# schematic_design.net
KiCad netlist of a schematic drawn in EasyEDA
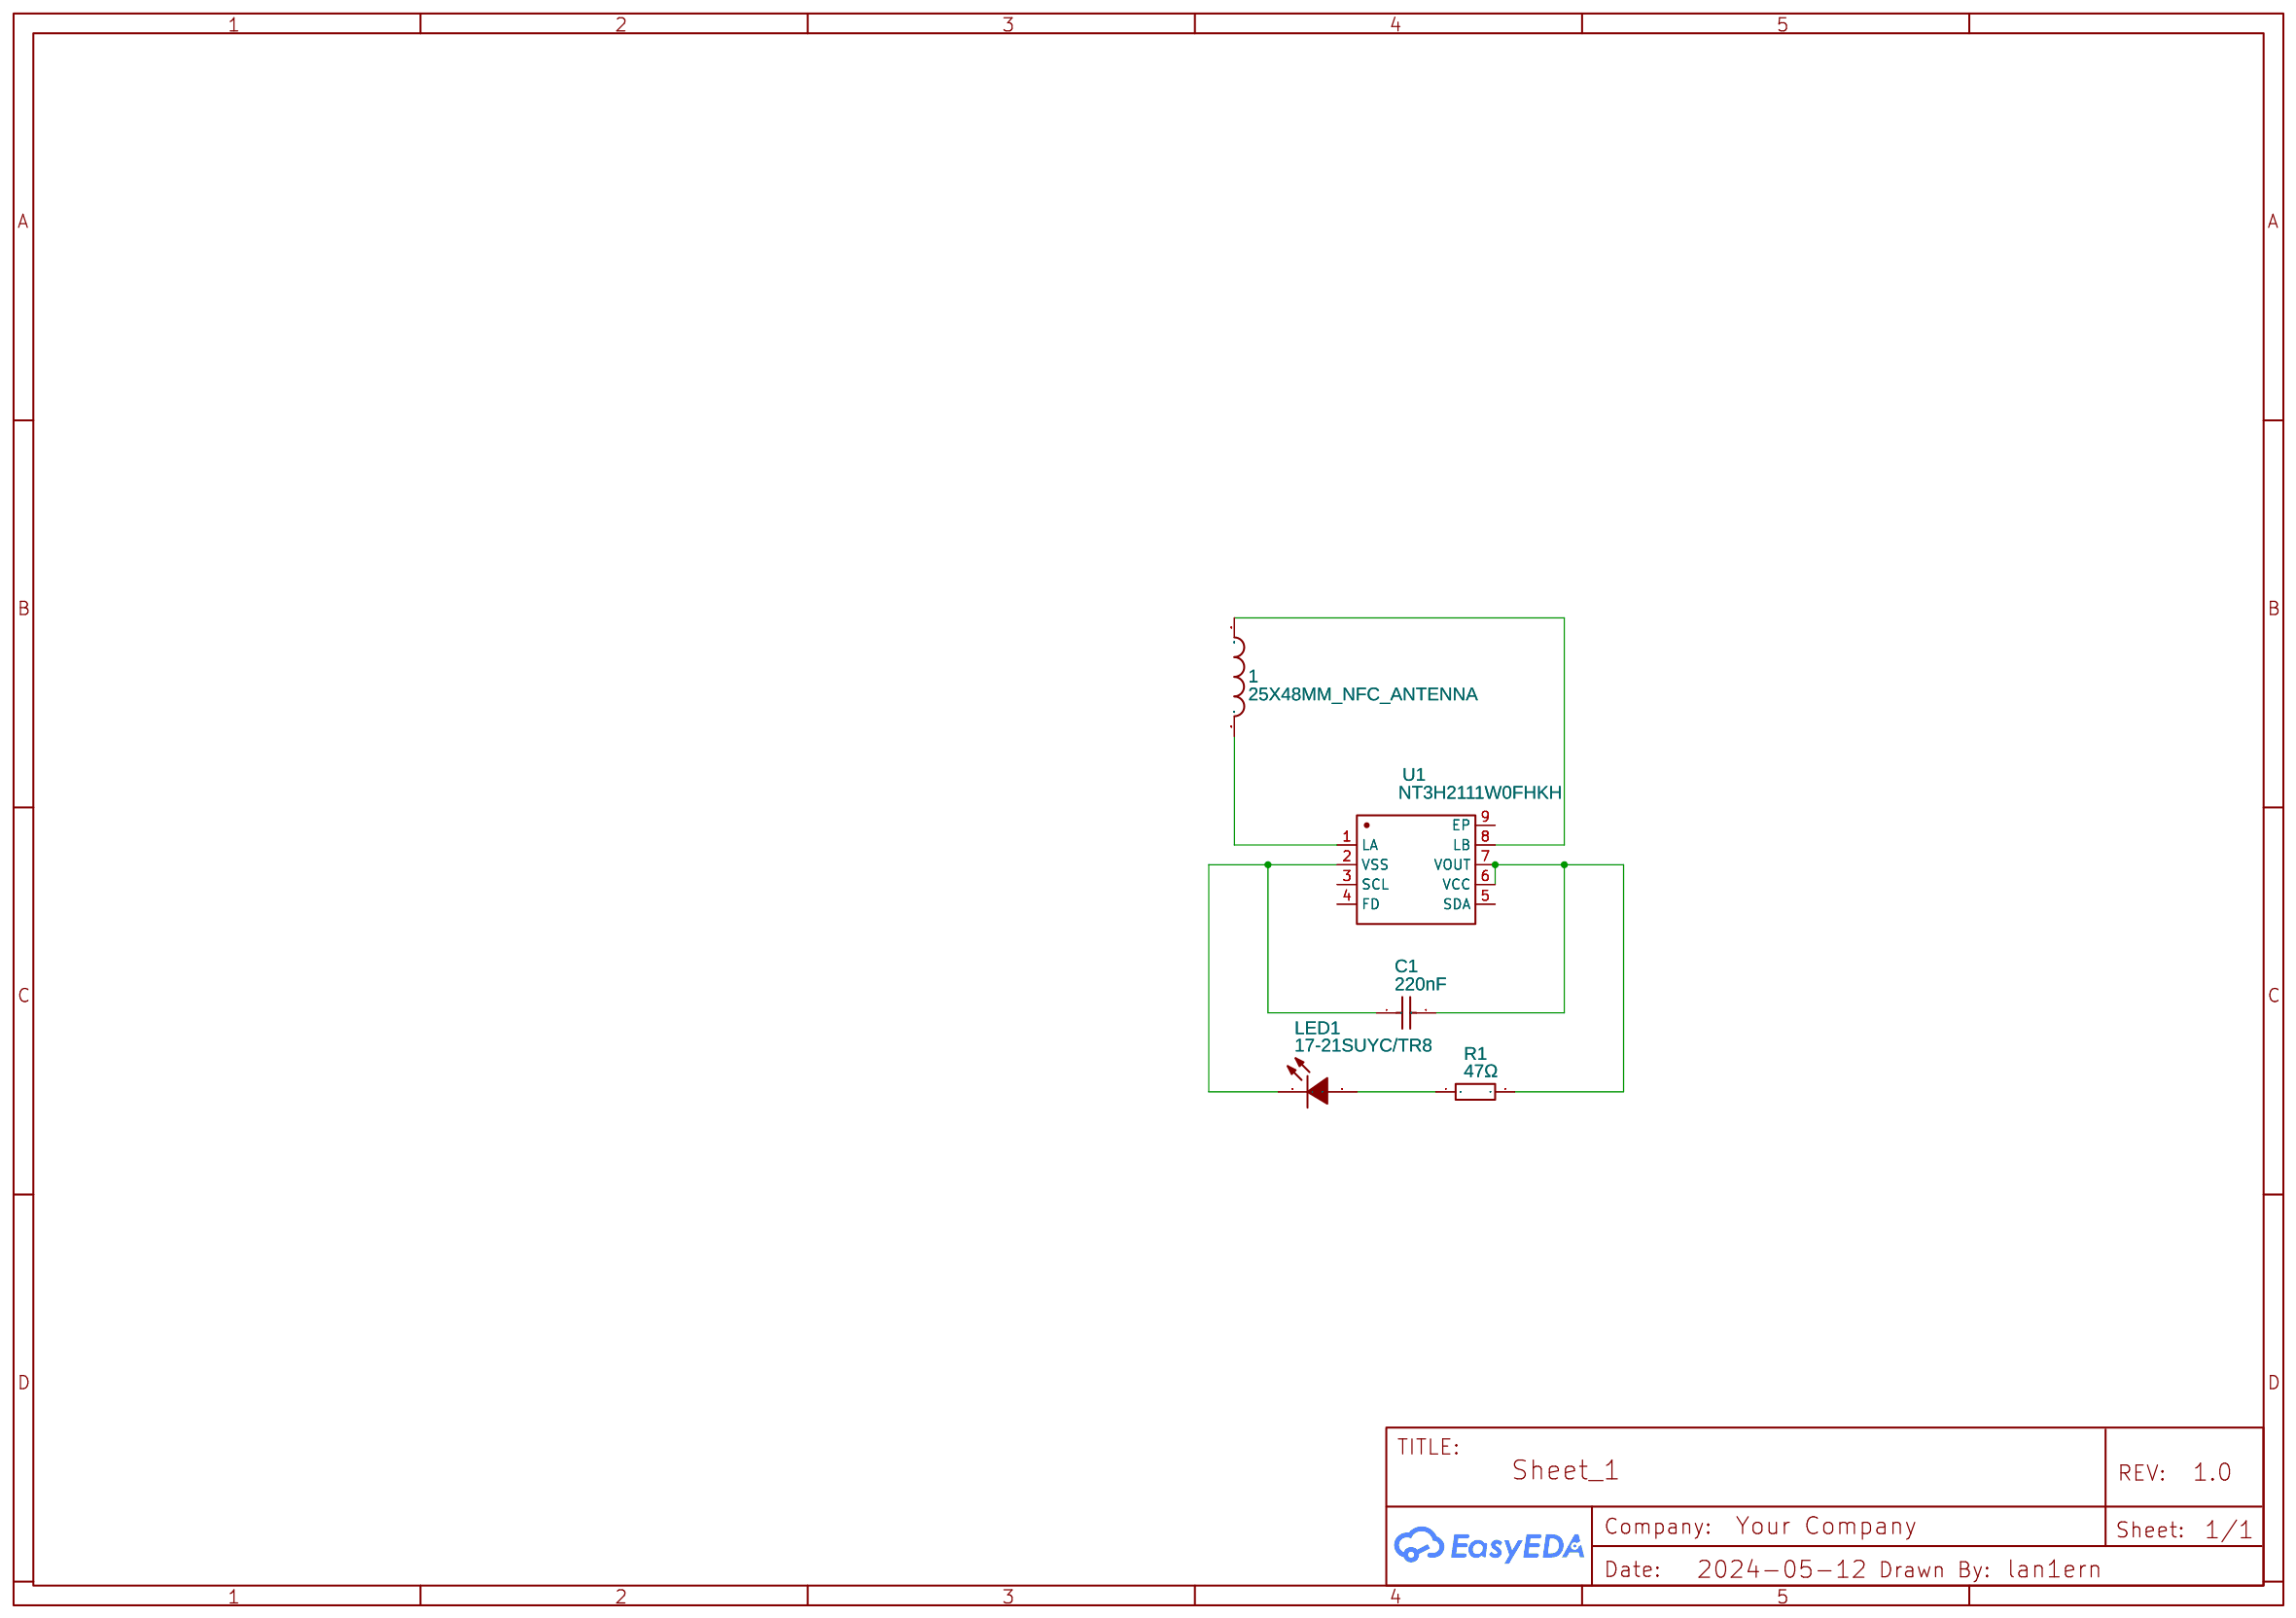
[diagram p0: schematic sheet]

(export (version "E")
  (design (tool "Eeschema 10.0.6"))
  (components
    (comp (ref "1") (value "25X48MM_NFC_ANTENNA") (libsource (lib "") (part "25X48MM_NFC_ANTENNA")))
    (comp (ref "C1")
      (value "220nF")
      (fields
        (field (name "Manufacturer Part") "CL10B224KA8NNNC")
        (field (name "Manufacturer") "SAMSUNG(三星)")
      )
      (libsource (lib "") (part "CL10B224KA8NNNC"))
    )
    (comp (ref "LED1")
      (value "17-21SUYC/TR8")
      (fields (field (name "Manufacturer Part") "KT-0805黄灯") (field (name "Manufacturer") "KENTO"))
      (libsource (lib "") (part "17-21SUYC/TR8"))
    )
    (comp (ref "R1")
      (value "47Ω")
      (fields
        (field (name "Manufacturer Part") "0603WAF470JT5E")
        (field (name "Manufacturer") "UNI-ROYAL(厚声)")
      )
      (libsource (lib "") (part "0603WAF470JT5E"))
    )
    (comp (ref "U1")
      (value "NT3H2111W0FHKH")
      (fields (field (name "Manufacturer") "NXP(恩智浦)"))
      (libsource (lib "") (part "NT3H2111W0FHKH"))
    )
  )
  (nets
    (net (code "1") (name "Net-(LED1-+)") (class "Default")
      (node (ref "LED1") (pin "1") (pinfunction "+_1") (pintype "unspecified"))
      (node (ref "R1") (pin "1") (pinfunction "1_1") (pintype "input"))
    )
    (net (code "2") (name "Net-(LED1--)") (class "Default")
      (node (ref "C1") (pin "1") (pinfunction "1_1") (pintype "input"))
      (node (ref "LED1") (pin "2") (pinfunction "-_2") (pintype "unspecified"))
      (node (ref "U1") (pin "2") (pinfunction "VSS_2") (pintype "unspecified"))
    )
    (net (code "3") (name "Net-(U1-LA)") (class "Default")
      (node (ref "1") (pin "P$2") (pinfunction "P$2_P$2") (pintype "bidirectional"))
      (node (ref "U1") (pin "1") (pinfunction "LA_1") (pintype "unspecified"))
    )
    (net (code "4") (name "Net-(U1-LB)") (class "Default")
      (node (ref "1") (pin "P$1") (pinfunction "P$1_P$1") (pintype "bidirectional"))
      (node (ref "U1") (pin "8") (pinfunction "LB_8") (pintype "unspecified"))
    )
    (net (code "5") (name "Net-(U1-VCC)") (class "Default")
      (node (ref "C1") (pin "2") (pinfunction "2_2") (pintype "input"))
      (node (ref "R1") (pin "2") (pinfunction "2_2") (pintype "input"))
      (node (ref "U1") (pin "6") (pinfunction "VCC_6") (pintype "unspecified"))
      (node (ref "U1") (pin "7") (pinfunction "VOUT_7") (pintype "unspecified"))
    )
    (net (code "6") (name "unconnected-(U1-EP-Pad9)") (class "Default")
      (node (ref "U1") (pin "9") (pinfunction "EP_9") (pintype "unspecified"))
    )
    (net (code "7") (name "unconnected-(U1-FD-Pad4)") (class "Default")
      (node (ref "U1") (pin "4") (pinfunction "FD_4") (pintype "unspecified"))
    )
    (net (code "8") (name "unconnected-(U1-SCL-Pad3)") (class "Default")
      (node (ref "U1") (pin "3") (pinfunction "SCL_3") (pintype "unspecified"))
    )
    (net (code "9") (name "unconnected-(U1-SDA-Pad5)") (class "Default")
      (node (ref "U1") (pin "5") (pinfunction "SDA_5") (pintype "unspecified"))
    )
  )
)
